# SJ2088POE_IMU.net
KiCad netlist of a schematic drawn in Altium Designer
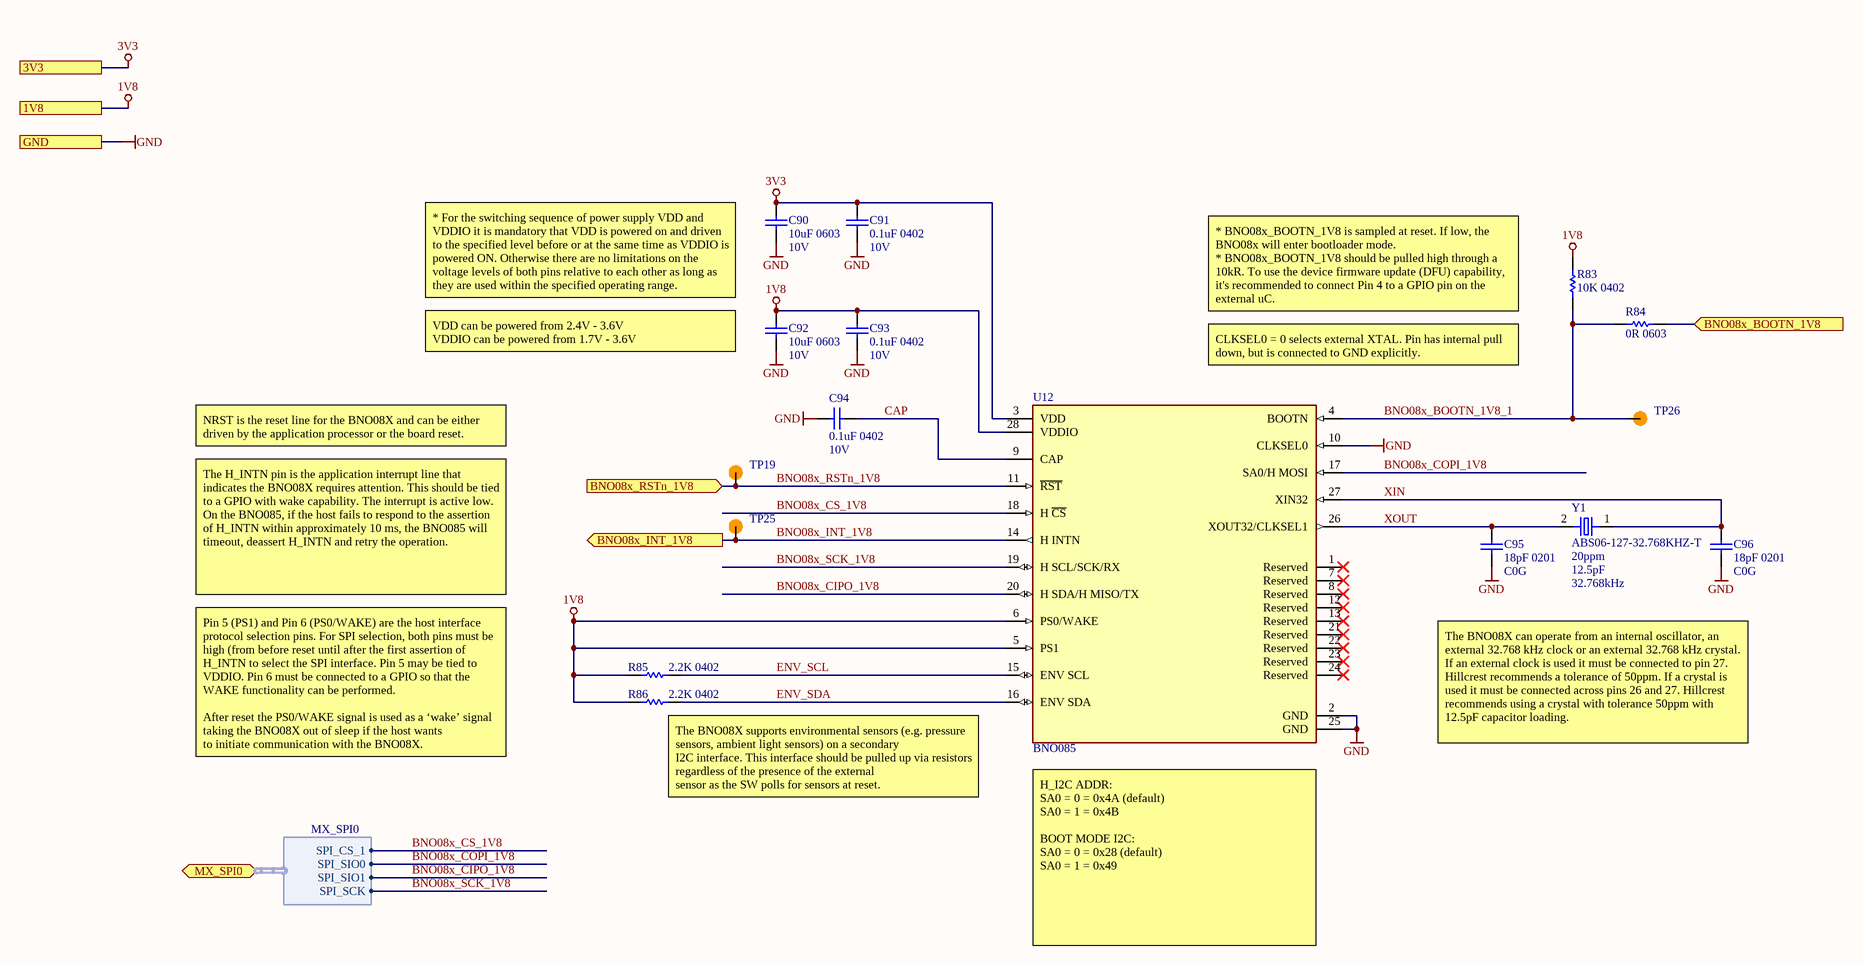
[diagram p0: SJ2088POE_IMU.SchDoc]

(export (version "E")
  (design (tool "Eeschema 10.0.6"))
  (components
    (comp (ref "C90")
      (value "10uF 0603")
      (footprint "CAP_Altium_Vault_Generic:CAPC0603(1608)100_L")
      (description "CAP CER 10UF 10V X5R 0603 20%")
      (fields (field (name "TOLERANCE") "20%") (field (name "VOLTAGE RATING") "10V"))
      (libsource (lib "LuxonisMaster") (part "GRM188R61A106ME69D"))
    )
    (comp (ref "C91")
      (value "0.1uF 0402")
      (footprint "CAP_Altium_Vault_Generic:CAPC0402(1005)70_L")
      (description "CAP CER 0.1UF 10V X7R 0402 5%")
      (fields (field (name "TOLERANCE") "5%") (field (name "VOLTAGE RATING") "10V"))
      (libsource (lib "LuxonisMaster") (part "GRM155R71A104JA01D"))
    )
    (comp (ref "C92")
      (value "10uF 0603")
      (footprint "CAP_Altium_Vault_Generic:CAPC0603(1608)100_L")
      (description "CAP CER 10UF 10V X5R 0603 20%")
      (fields (field (name "TOLERANCE") "20%") (field (name "VOLTAGE RATING") "10V"))
      (libsource (lib "LuxonisMaster") (part "GRM188R61A106ME69D"))
    )
    (comp (ref "C93")
      (value "0.1uF 0402")
      (footprint "CAP_Altium_Vault_Generic:CAPC0402(1005)70_L")
      (description "CAP CER 0.1UF 10V X7R 0402 5%")
      (fields (field (name "TOLERANCE") "5%") (field (name "VOLTAGE RATING") "10V"))
      (libsource (lib "LuxonisMaster") (part "GRM155R71A104JA01D"))
    )
    (comp (ref "C94")
      (value "0.1uF 0402")
      (footprint "CAP_Altium_Vault_Generic:CAPC0402(1005)70_L")
      (description "CAP CER 0.1UF 10V X7R 0402 5%")
      (fields (field (name "TOLERANCE") "5%") (field (name "VOLTAGE RATING") "10V"))
      (libsource (lib "LuxonisMaster") (part "GRM155R71A104JA01D"))
    )
    (comp (ref "C95")
      (value "18pF 0201")
      (footprint "CAP_Altium_Vault_Generic:CAPC0201(0603)33_L")
      (description "Cap Ceramic 18pF 25V C0G 1% Pad SMD 0201 125C T/R")
      (fields (field (name "TOLERANCE") "1%") (field (name "DIELECTRIC") "C0G"))
      (libsource (lib "BW1092_R0M0E0") (part "GRM0335C1E180FA01D"))
    )
    (comp (ref "C96")
      (value "18pF 0201")
      (footprint "CAP_Altium_Vault_Generic:CAPC0201(0603)33_L")
      (description "Cap Ceramic 18pF 25V C0G 1% Pad SMD 0201 125C T/R")
      (fields (field (name "TOLERANCE") "1%") (field (name "DIELECTRIC") "C0G"))
      (libsource (lib "BW1092_R0M0E0") (part "GRM0335C1E180FA01D"))
    )
    (comp (ref "R83")
      (value "10K 0402")
      (footprint "RES_Altium_Vault_Generic:RESC0402(1005)_L")
      (fields (field (name "TOLERANCE") "1%"))
      (libsource (lib "LuxonisMaster") (part "RC0402FR-1310KL"))
    )
    (comp (ref "R84")
      (value "0R 0603")
      (footprint "RES_Altium_Vault_Generic:RESC0603(1608)_L")
      (fields (field (name "TOLERANCE") "5%"))
      (libsource (lib "LuxonisMaster") (part "CRCW06030000Z0EA"))
    )
    (comp (ref "R85")
      (value "2.2K 0402")
      (footprint "RES_Altium_Vault_Generic:RESC0402(1005)_L")
      (description "RES SMD 2.2K OHM 1% 1/16W 0402")
      (fields (field (name "TOLERANCE") "1%"))
      (libsource (lib "LuxonisMaster") (part "RC0402FR-072K2L"))
    )
    (comp (ref "R86")
      (value "2.2K 0402")
      (footprint "RES_Altium_Vault_Generic:RESC0402(1005)_L")
      (description "RES SMD 2.2K OHM 1% 1/16W 0402")
      (fields (field (name "TOLERANCE") "1%"))
      (libsource (lib "LuxonisMaster") (part "RC0402FR-072K2L"))
    )
    (comp (ref "TP19")
      (value "TP100_200_NS")
      (footprint "LuxonisMaster:TP100_200_NS")
      (libsource (lib "LuxonisMaster") (part "TEST_POINT"))
    )
    (comp (ref "TP25")
      (value "TP100_200_NS")
      (footprint "LuxonisMaster:TP100_200_NS")
      (libsource (lib "LuxonisMaster") (part "TEST_POINT"))
    )
    (comp (ref "TP26")
      (value "TP100_200_NS")
      (footprint "LuxonisMaster:TP100_200_NS")
      (libsource (lib "LuxonisMaster") (part "TEST_POINT"))
    )
    (comp (ref "U12")
      (value "BNO085")
      (footprint "BW1092_R0M0E0:BNO085")
      (description "IMU ACCEL/GYRO/MAG I2C 32BIT")
      (libsource (lib "BW1092_R0M0E0") (part "BNO085"))
    )
    (comp (ref "Y1")
      (value "ABS06-127-32.768KHZ-T")
      (footprint "BW1092_R0M0E0:ABS06-127-32.768KHZ-T")
      (description "CRYSTAL 32.768kHz ±20ppm Crystal 12.5pF 90 kOhms 2-SMD, No Lead")
      (fields
        (field (name "FREQUENCY TOLERANCE") "20ppm")
        (field (name "LOAD CAPACITANCE") "12.5pF")
        (field (name "FREQUENCY") "32.768kHz")
      )
      (libsource (lib "BW1092_R0M0E0") (part "ABS06-127-32.768KHZ-T"))
    )
  )
  (nets
    (net (code "2") (name "/BNO08x_BOOTN_1V8") (class "Default")
      (node (ref "R84") (pin "2") (pinfunction "2_2") (pintype "passive"))
    )
    (net (code "3") (name "/BNO08x_BOOTN_1V8_1") (class "Default")
      (node (ref "R83") (pin "1") (pinfunction "1_1") (pintype "passive"))
      (node (ref "R84") (pin "1") (pinfunction "1_1") (pintype "passive"))
      (node (ref "TP26") (pin "1") (pintype "passive"))
      (node (ref "U12") (pin "4") (pinfunction "BOOTN_4") (pintype "input"))
    )
    (net (code "4") (name "/BNO08x_CIPO_1V8") (class "Default")
      (node (ref "U12") (pin "20") (pinfunction "H_SDA/H_MISO/TX_20") (pintype "bidirectional"))
    )
    (net (code "5") (name "/BNO08x_COPI_1V8") (class "Default")
      (node (ref "U12") (pin "17") (pinfunction "SA0/H_MOSI_17") (pintype "input"))
    )
    (net (code "6") (name "/BNO08x_CS_1V8") (class "Default")
      (node (ref "U12") (pin "18") (pinfunction "H_~{CS}_18") (pintype "input"))
    )
    (net (code "7") (name "/BNO08x_INT_1V8") (class "Default")
      (node (ref "TP25") (pin "1") (pintype "passive"))
      (node (ref "U12") (pin "14") (pinfunction "H_INTN_14") (pintype "output"))
    )
    (net (code "8") (name "/BNO08x_RSTn_1V8") (class "Default")
      (node (ref "TP19") (pin "1") (pintype "passive"))
      (node (ref "U12") (pin "11") (pinfunction "~{RST}_11") (pintype "input"))
    )
    (net (code "9") (name "/BNO08x_SCK_1V8") (class "Default")
      (node (ref "U12") (pin "19") (pinfunction "H_SCL/SCK/RX_19") (pintype "bidirectional"))
    )
    (net (code "10") (name "/CAP") (class "Default")
      (node (ref "C94") (pin "1") (pinfunction "1_1") (pintype "passive"))
      (node (ref "U12") (pin "9") (pinfunction "CAP_9") (pintype "passive"))
    )
    (net (code "11") (name "/ENV_SCL") (class "Default")
      (node (ref "R85") (pin "2") (pinfunction "2_2") (pintype "passive"))
      (node (ref "U12") (pin "15") (pinfunction "ENV_SCL_15") (pintype "bidirectional"))
    )
    (net (code "12") (name "/ENV_SDA") (class "Default")
      (node (ref "R86") (pin "2") (pinfunction "2_2") (pintype "passive"))
      (node (ref "U12") (pin "16") (pinfunction "ENV_SDA_16") (pintype "bidirectional"))
    )
    (net (code "13") (name "/XIN") (class "Default")
      (node (ref "C96") (pin "2") (pinfunction "2_2") (pintype "passive"))
      (node (ref "U12") (pin "27") (pinfunction "XIN32_27") (pintype "input"))
      (node (ref "Y1") (pin "1") (pinfunction "1_1") (pintype "passive"))
    )
    (net (code "14") (name "/XOUT") (class "Default")
      (node (ref "C95") (pin "2") (pinfunction "2_2") (pintype "passive"))
      (node (ref "U12") (pin "26") (pinfunction "XOUT32/CLKSEL1_26") (pintype "output"))
      (node (ref "Y1") (pin "2") (pinfunction "2_2") (pintype "passive"))
    )
    (net (code "16") (name "1V8") (class "Default")
      (node (ref "C92") (pin "2") (pinfunction "2_2") (pintype "passive"))
      (node (ref "C93") (pin "2") (pinfunction "2_2") (pintype "passive"))
      (node (ref "R83") (pin "2") (pinfunction "2_2") (pintype "passive"))
      (node (ref "R85") (pin "1") (pinfunction "1_1") (pintype "passive"))
      (node (ref "R86") (pin "1") (pinfunction "1_1") (pintype "passive"))
      (node (ref "U12") (pin "28") (pinfunction "VDDIO_28") (pintype "power_in"))
      (node (ref "U12") (pin "5") (pinfunction "PS1_5") (pintype "input"))
      (node (ref "U12") (pin "6") (pinfunction "PS0/WAKE_6") (pintype "input"))
    )
    (net (code "17") (name "3V3") (class "Default")
      (node (ref "C90") (pin "2") (pinfunction "2_2") (pintype "passive"))
      (node (ref "C91") (pin "2") (pinfunction "2_2") (pintype "passive"))
      (node (ref "U12") (pin "3") (pinfunction "VDD_3") (pintype "power_in"))
    )
    (net (code "18") (name "GND") (class "Default")
      (node (ref "C90") (pin "1") (pinfunction "1_1") (pintype "passive"))
      (node (ref "C91") (pin "1") (pinfunction "1_1") (pintype "passive"))
      (node (ref "C92") (pin "1") (pinfunction "1_1") (pintype "passive"))
      (node (ref "C93") (pin "1") (pinfunction "1_1") (pintype "passive"))
      (node (ref "C94") (pin "2") (pinfunction "2_2") (pintype "passive"))
      (node (ref "C95") (pin "1") (pinfunction "1_1") (pintype "passive"))
      (node (ref "C96") (pin "1") (pinfunction "1_1") (pintype "passive"))
      (node (ref "U12") (pin "10") (pinfunction "CLKSEL0_10") (pintype "input"))
      (node (ref "U12") (pin "2") (pinfunction "GND_2") (pintype "power_in"))
      (node (ref "U12") (pin "25") (pinfunction "GND_25") (pintype "power_in"))
    )
    (net (code "19") (name "unconnected-(U12-Reserved-Pad1)") (class "Default")
      (node (ref "U12") (pin "1") (pinfunction "Reserved_1") (pintype "passive+no_connect"))
    )
    (net (code "20") (name "unconnected-(U12-Reserved-Pad7)") (class "Default")
      (node (ref "U12") (pin "7") (pinfunction "Reserved_7") (pintype "passive+no_connect"))
    )
    (net (code "21") (name "unconnected-(U12-Reserved-Pad8)") (class "Default")
      (node (ref "U12") (pin "8") (pinfunction "Reserved_8") (pintype "passive+no_connect"))
    )
    (net (code "22") (name "unconnected-(U12-Reserved-Pad12)") (class "Default")
      (node (ref "U12") (pin "12") (pinfunction "Reserved_12") (pintype "passive+no_connect"))
    )
    (net (code "23") (name "unconnected-(U12-Reserved-Pad13)") (class "Default")
      (node (ref "U12") (pin "13") (pinfunction "Reserved_13") (pintype "passive+no_connect"))
    )
    (net (code "24") (name "unconnected-(U12-Reserved-Pad21)") (class "Default")
      (node (ref "U12") (pin "21") (pinfunction "Reserved_21") (pintype "passive+no_connect"))
    )
    (net (code "25") (name "unconnected-(U12-Reserved-Pad22)") (class "Default")
      (node (ref "U12") (pin "22") (pinfunction "Reserved_22") (pintype "passive+no_connect"))
    )
    (net (code "26") (name "unconnected-(U12-Reserved-Pad23)") (class "Default")
      (node (ref "U12") (pin "23") (pinfunction "Reserved_23") (pintype "passive+no_connect"))
    )
    (net (code "27") (name "unconnected-(U12-Reserved-Pad24)") (class "Default")
      (node (ref "U12") (pin "24") (pinfunction "Reserved_24") (pintype "passive+no_connect"))
    )
  )
)
